# analog_homoThermistor_1xChannel_R1.net
KiCad netlist of a schematic drawn in EAGLE
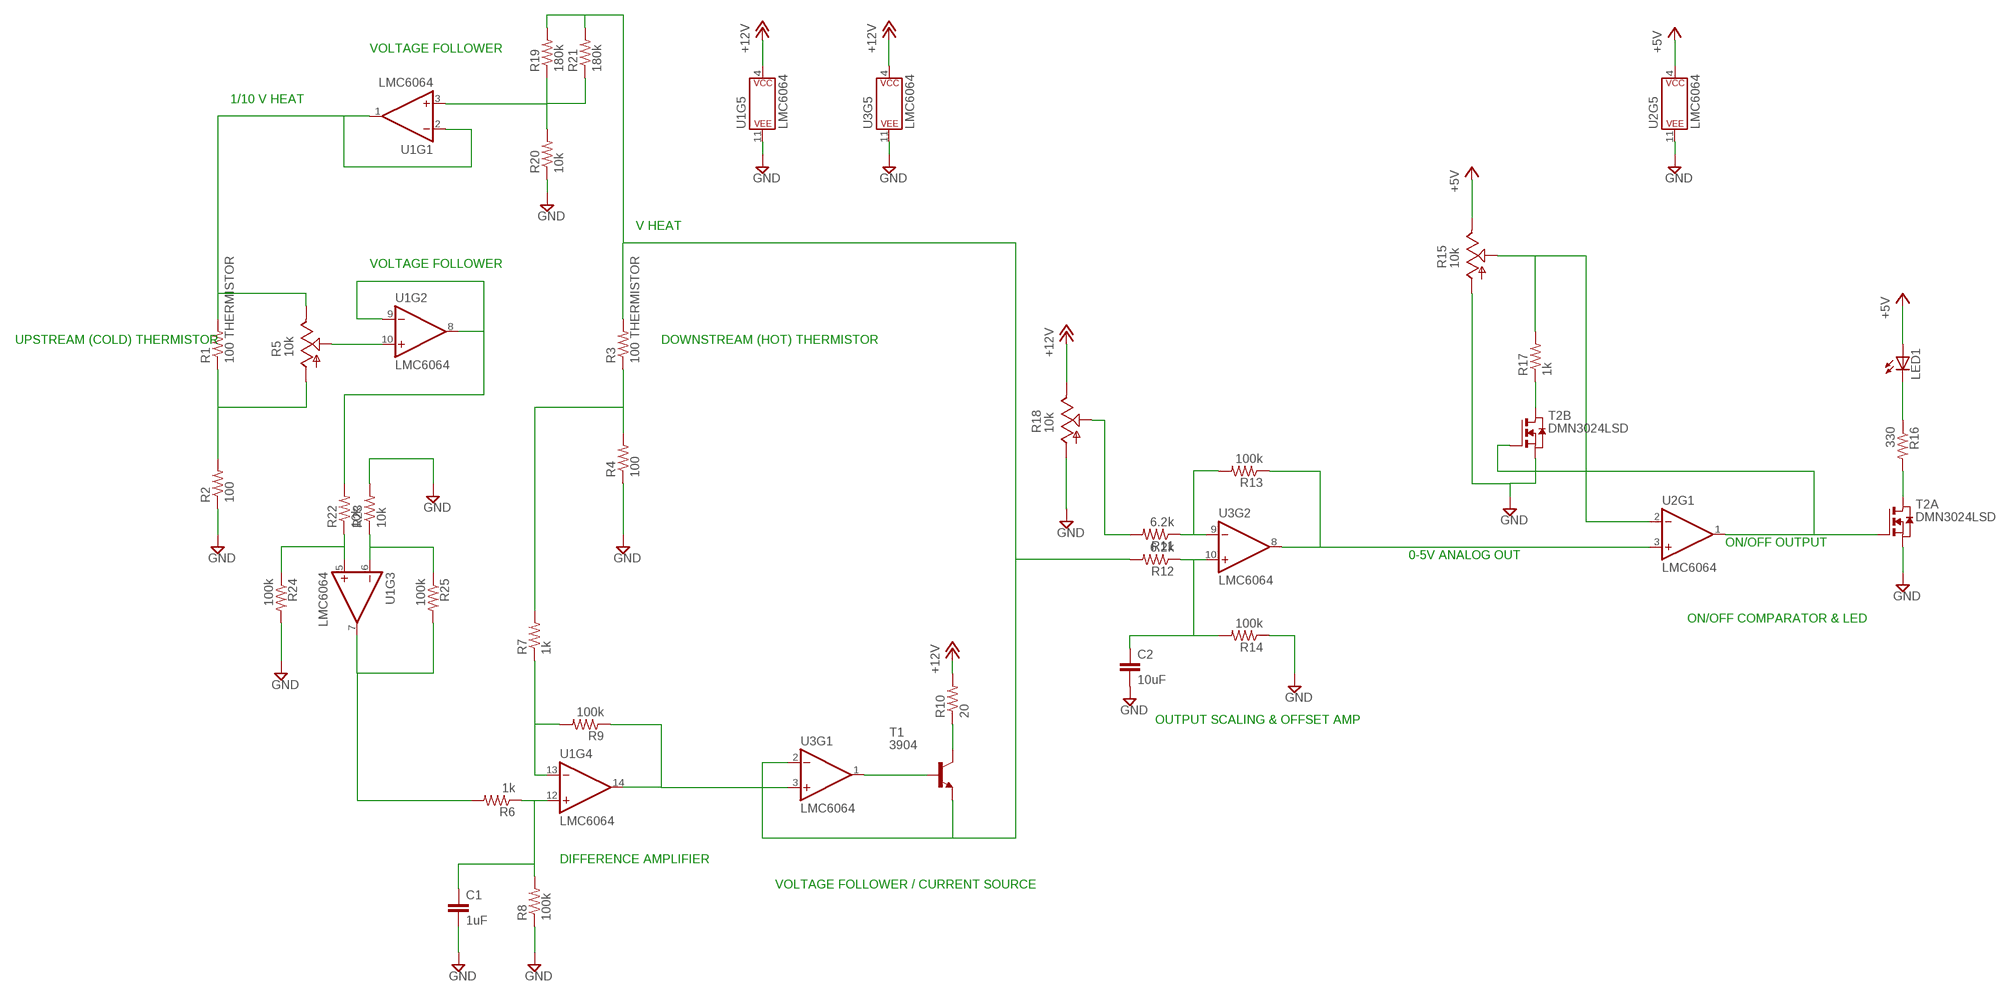
[diagram p0: schematic, sheet 1]

(export (version "E")
  (design (tool "Eeschema 10.0.6"))
  (components
    (comp (ref "C1")
      (value "1uF")
      (footprint "eagle-import:C0603")
      (fields
        (field (name "MF") "Murata Electronics North America")
        (field (name "MPN") "GRM188R61C105KA93D")
      )
      (libsource (lib "eagle-import") (part "C-EUC0603"))
    )
    (comp (ref "C2")
      (value "10uF")
      (footprint "eagle-import:C0603")
      (fields
        (field (name "MF") "Murata Electronics North America")
        (field (name "MPN") "GRM188C81C106MA73D")
      )
      (libsource (lib "eagle-import") (part "C-EUC0603"))
    )
    (comp (ref "LED1")
      (value "LEDCHIPLED_1206")
      (footprint "eagle-import:CHIPLED_1206")
      (fields (field (name "MF") "Lite-On Inc.") (field (name "MPN") "LTST-C150GKT"))
      (libsource (lib "eagle-import") (part "LEDCHIPLED_1206"))
    )
    (comp (ref "R1")
      (value "100 THERMISTOR")
      (footprint "eagle-import:R0603")
      (fields
        (field (name "DISTR") "Digikey")
        (field (name "DISTRPN") "490-2434-1-ND")
        (field (name "MF") "Murata Electronics North America")
        (field (name "MPN") "NCP18XF101J03RB")
      )
      (libsource (lib "eagle-import") (part "R-US_R0603"))
    )
    (comp (ref "R2")
      (value "100")
      (footprint "eagle-import:R0603")
      (fields (field (name "MF") "Panasonic Electronic Components") (field (name "MPN") "ERJ-PA3F1000V"))
      (libsource (lib "eagle-import") (part "R-US_R0603"))
    )
    (comp (ref "R3")
      (value "100 THERMISTOR")
      (footprint "eagle-import:R0603")
      (fields
        (field (name "DISTR") "Digikey")
        (field (name "DISTRPN") "490-2434-1-ND")
        (field (name "MF") "Murata Electronics North America")
        (field (name "MPN") "NCP18XF101J03RB")
      )
      (libsource (lib "eagle-import") (part "R-US_R0603"))
    )
    (comp (ref "R4")
      (value "100")
      (footprint "eagle-import:R0603")
      (fields (field (name "MF") "Panasonic Electronic Components") (field (name "MPN") "ERJ-PA3F1000V"))
      (libsource (lib "eagle-import") (part "R-US_R0603"))
    )
    (comp (ref "R5")
      (value "10k")
      (footprint "eagle-import:SM-42_43W")
      (fields (field (name "MF") "Copal Electronics Inc.") (field (name "MPN") "SM-42TW103"))
      (libsource (lib "eagle-import") (part "TRIM_US-SM-42/43W"))
    )
    (comp (ref "R6")
      (value "1k")
      (footprint "eagle-import:R0603")
      (fields (field (name "MF") "Panasonic Electronic Components") (field (name "MPN") "ERJ-PA3F1001V"))
      (libsource (lib "eagle-import") (part "R-US_R0603"))
    )
    (comp (ref "R7")
      (value "1k")
      (footprint "eagle-import:R0603")
      (fields (field (name "MF") "Panasonic Electronic Components") (field (name "MPN") "ERJ-PA3F1001V"))
      (libsource (lib "eagle-import") (part "R-US_R0603"))
    )
    (comp (ref "R8")
      (value "100k")
      (footprint "eagle-import:R0603")
      (fields (field (name "MF") "Panasonic Electronic Components") (field (name "MPN") "ERJ-PA3F1003V"))
      (libsource (lib "eagle-import") (part "R-US_R0603"))
    )
    (comp (ref "R9")
      (value "100k")
      (footprint "eagle-import:R0603")
      (fields (field (name "MF") "Panasonic Electronic Components") (field (name "MPN") "ERJ-PA3F1003V"))
      (libsource (lib "eagle-import") (part "R-US_R0603"))
    )
    (comp (ref "R10")
      (value "20")
      (footprint "eagle-import:R0603")
      (fields (field (name "MF") "Panasonic Electronic Components") (field (name "MPN") "ERJ-PA3F20R0V"))
      (libsource (lib "eagle-import") (part "R-US_R0603"))
    )
    (comp (ref "R11")
      (value "6.2k")
      (footprint "eagle-import:R0603")
      (fields (field (name "MF") "Panasonic Electronic Components") (field (name "MPN") "ERJ-PA3F6201V"))
      (libsource (lib "eagle-import") (part "R-US_R0603"))
    )
    (comp (ref "R12")
      (value "6.2k")
      (footprint "eagle-import:R0603")
      (fields (field (name "MF") "Panasonic Electronic Components") (field (name "MPN") "ERJ-PA3F6201V"))
      (libsource (lib "eagle-import") (part "R-US_R0603"))
    )
    (comp (ref "R13")
      (value "100k")
      (footprint "eagle-import:R0603")
      (fields (field (name "MF") "Panasonic Electronic Components") (field (name "MPN") "ERJ-PA3F1003V"))
      (libsource (lib "eagle-import") (part "R-US_R0603"))
    )
    (comp (ref "R14")
      (value "100k")
      (footprint "eagle-import:R0603")
      (fields (field (name "MF") "Panasonic Electronic Components") (field (name "MPN") "ERJ-PA3F1003V"))
      (libsource (lib "eagle-import") (part "R-US_R0603"))
    )
    (comp (ref "R15")
      (value "10k")
      (footprint "eagle-import:SM-42_43W")
      (fields (field (name "MF") "Copal Electronics Inc.") (field (name "MPN") "SM-42TW103"))
      (libsource (lib "eagle-import") (part "TRIM_US-SM-42/43W"))
    )
    (comp (ref "R16")
      (value "330")
      (footprint "eagle-import:R0603")
      (fields (field (name "MF") "Panasonic Electronic Components") (field (name "MPN") "ERJ-PA3F3300V"))
      (libsource (lib "eagle-import") (part "R-US_R0603"))
    )
    (comp (ref "R17")
      (value "1k")
      (footprint "eagle-import:R0603")
      (fields (field (name "MF") "Panasonic Electronic Components") (field (name "MPN") "ERJ-PA3F1001V"))
      (libsource (lib "eagle-import") (part "R-US_R0603"))
    )
    (comp (ref "R18")
      (value "10k")
      (footprint "eagle-import:SM-42_43W")
      (fields (field (name "MF") "Copal Electronics Inc.") (field (name "MPN") "SM-42TW103"))
      (libsource (lib "eagle-import") (part "TRIM_US-SM-42/43W"))
    )
    (comp (ref "R19")
      (value "180k")
      (footprint "eagle-import:R0603")
      (fields (field (name "MF") "Panasonic Electronic Components") (field (name "MPN") "ERJ-PA3F1803V"))
      (libsource (lib "eagle-import") (part "R-US_R0603"))
    )
    (comp (ref "R20")
      (value "10k")
      (footprint "eagle-import:R0603")
      (fields (field (name "MF") "Panasonic Electronic Components") (field (name "MPN") "ERJ-PA3F1002V"))
      (libsource (lib "eagle-import") (part "R-US_R0603"))
    )
    (comp (ref "R21")
      (value "180k")
      (footprint "eagle-import:R0603")
      (fields (field (name "MF") "Panasonic Electronic Components") (field (name "MPN") "ERJ-PA3F1803V"))
      (libsource (lib "eagle-import") (part "R-US_R0603"))
    )
    (comp (ref "R22")
      (value "10k")
      (footprint "eagle-import:R0603")
      (fields (field (name "MF") "Panasonic Electronic Components") (field (name "MPN") "ERJ-PA3F1002V"))
      (libsource (lib "eagle-import") (part "R-US_R0603"))
    )
    (comp (ref "R23")
      (value "10k")
      (footprint "eagle-import:R0603")
      (fields (field (name "MF") "Panasonic Electronic Components") (field (name "MPN") "ERJ-PA3F1002V"))
      (libsource (lib "eagle-import") (part "R-US_R0603"))
    )
    (comp (ref "R24")
      (value "100k")
      (footprint "eagle-import:R0603")
      (fields (field (name "MF") "Panasonic Electronic Components") (field (name "MPN") "ERJ-PA3F1003V"))
      (libsource (lib "eagle-import") (part "R-US_R0603"))
    )
    (comp (ref "R25")
      (value "100k")
      (footprint "eagle-import:R0603")
      (fields (field (name "MF") "Panasonic Electronic Components") (field (name "MPN") "ERJ-PA3F1003V"))
      (libsource (lib "eagle-import") (part "R-US_R0603"))
    )
    (comp (ref "T1")
      (value "3904")
      (footprint "eagle-import:SOT23-BEC")
      (fields (field (name "MF") "Fairchild/ON Semiconductor") (field (name "MPN") "MMBT3904"))
      (libsource (lib "eagle-import") (part "-NPN-SOT23-BECMMBT3904LT1"))
    )
    (comp (ref "T2")
      (value "DMN3024LSD")
      (footprint "eagle-import:SO8")
      (fields
        (field (name "MF") "Diodes Incorporated")
        (field (name "MPN") "DMN3024LSD-13")
        (field (name "DISTR") "Digikey")
        (field (name "DISTRPN") "DMN3024LSD-13DICT-ND")
      )
      (libsource (lib "eagle-import") (part "DMN3024LSD"))
    )
    (comp (ref "U1")
      (value "LMC6064")
      (footprint "eagle-import:SO14")
      (fields
        (field (name "DISTR") "Digikey")
        (field (name "DISTRPN") "296-35438-1-ND")
        (field (name "MF") "Texas Instruments")
        (field (name "MPN") "LMC6064AIMX/NOPB")
      )
      (libsource (lib "eagle-import") (part "LMC6064"))
    )
    (comp (ref "U2")
      (value "LMC6064")
      (footprint "eagle-import:SO14")
      (fields
        (field (name "MF") "Texas Instruments")
        (field (name "MPN") "LMC6064AIMX/NOPB")
        (field (name "DISTR") "Digikey")
        (field (name "DISTRPN") "296-35438-1-ND")
      )
      (libsource (lib "eagle-import") (part "LMC6064"))
    )
    (comp (ref "U3")
      (value "LMC6064")
      (footprint "eagle-import:SO14")
      (fields
        (field (name "DISTR") "Digikey")
        (field (name "DISTRPN") "296-35438-1-ND")
        (field (name "MF") "Texas Instruments")
        (field (name "MPN") "LMC6064AIMX/NOPB")
      )
      (libsource (lib "eagle-import") (part "LMC6064"))
    )
  )
  (nets
    (net (code "1") (name "+5V") (class "Default")
      (node (ref "LED1") (pin "A") (pinfunction "A_A") (pintype "passive"))
      (node (ref "R15") (pin "3") (pinfunction "E_3") (pintype "passive"))
      (node (ref "U2") (pin "4") (pinfunction "P$V+_4") (pintype "bidirectional"))
    )
    (net (code "2") (name "+12V") (class "Default")
      (node (ref "R10") (pin "2") (pinfunction "2_2") (pintype "passive"))
      (node (ref "R18") (pin "3") (pinfunction "E_3") (pintype "passive"))
      (node (ref "U1") (pin "4") (pinfunction "P$V+_4") (pintype "bidirectional"))
      (node (ref "U3") (pin "4") (pinfunction "P$V+_4") (pintype "bidirectional"))
    )
    (net (code "3") (name "GND") (class "Default")
      (node (ref "C1") (pin "2") (pinfunction "2_2") (pintype "passive"))
      (node (ref "C2") (pin "2") (pinfunction "2_2") (pintype "passive"))
      (node (ref "R14") (pin "1") (pinfunction "1_1") (pintype "passive"))
      (node (ref "R15") (pin "1") (pinfunction "A_1") (pintype "passive"))
      (node (ref "R18") (pin "1") (pinfunction "A_1") (pintype "passive"))
      (node (ref "R2") (pin "1") (pinfunction "1_1") (pintype "passive"))
      (node (ref "R20") (pin "1") (pinfunction "1_1") (pintype "passive"))
      (node (ref "R23") (pin "2") (pinfunction "2_2") (pintype "passive"))
      (node (ref "R24") (pin "2") (pinfunction "2_2") (pintype "passive"))
      (node (ref "R4") (pin "1") (pinfunction "1_1") (pintype "passive"))
      (node (ref "R8") (pin "1") (pinfunction "1_1") (pintype "passive"))
      (node (ref "T2") (pin "1") (pinfunction "S_1") (pintype "passive"))
      (node (ref "T2") (pin "3") (pinfunction "S_3") (pintype "passive"))
      (node (ref "U1") (pin "11") (pinfunction "P$V-_11") (pintype "bidirectional"))
      (node (ref "U2") (pin "11") (pinfunction "P$V-_11") (pintype "bidirectional"))
      (node (ref "U3") (pin "11") (pinfunction "P$V-_11") (pintype "bidirectional"))
    )
    (net (code "4") (name "Net-(LED1-PadC)") (class "Default")
      (node (ref "LED1") (pin "C") (pinfunction "C_C") (pintype "passive"))
      (node (ref "R16") (pin "1") (pinfunction "1_1") (pintype "passive"))
    )
    (net (code "5") (name "Net-(R3-Pad1)") (class "Default")
      (node (ref "R3") (pin "1") (pinfunction "1_1") (pintype "passive"))
      (node (ref "R4") (pin "2") (pinfunction "2_2") (pintype "passive"))
      (node (ref "R7") (pin "2") (pinfunction "2_2") (pintype "passive"))
    )
    (net (code "6") (name "Net-(R5-A)") (class "Default")
      (node (ref "R1") (pin "1") (pinfunction "1_1") (pintype "passive"))
      (node (ref "R2") (pin "2") (pinfunction "2_2") (pintype "passive"))
      (node (ref "R5") (pin "1") (pinfunction "A_1") (pintype "passive"))
    )
    (net (code "7") (name "Net-(R5-E)") (class "Default")
      (node (ref "R1") (pin "2") (pinfunction "2_2") (pintype "passive"))
      (node (ref "R5") (pin "3") (pinfunction "E_3") (pintype "passive"))
      (node (ref "U1") (pin "1") (pinfunction "OUT_1") (pintype "output"))
      (node (ref "U1") (pin "2") (pinfunction "-IN_2") (pintype "input"))
    )
    (net (code "8") (name "Net-(R5-S)") (class "Default")
      (node (ref "R5") (pin "2") (pinfunction "S_2") (pintype "passive"))
      (node (ref "U1") (pin "10") (pinfunction "+IN_10") (pintype "input"))
    )
    (net (code "9") (name "Net-(R10-Pad1)") (class "Default")
      (node (ref "R10") (pin "1") (pinfunction "1_1") (pintype "passive"))
      (node (ref "T1") (pin "C") (pinfunction "C_C") (pintype "passive"))
    )
    (net (code "10") (name "Net-(R15-S)") (class "Default")
      (node (ref "R15") (pin "2") (pinfunction "S_2") (pintype "passive"))
      (node (ref "R17") (pin "2") (pinfunction "2_2") (pintype "passive"))
      (node (ref "U2") (pin "2") (pinfunction "-IN_2") (pintype "input"))
    )
    (net (code "11") (name "Net-(R16-Pad2)") (class "Default")
      (node (ref "R16") (pin "2") (pinfunction "2_2") (pintype "passive"))
      (node (ref "T2") (pin "7") (pinfunction "D_7") (pintype "passive"))
      (node (ref "T2") (pin "8") (pinfunction "D_8") (pintype "passive"))
    )
    (net (code "12") (name "Net-(R17-Pad1)") (class "Default")
      (node (ref "R17") (pin "1") (pinfunction "1_1") (pintype "passive"))
      (node (ref "T2") (pin "5") (pinfunction "D_5") (pintype "passive"))
      (node (ref "T2") (pin "6") (pinfunction "D_6") (pintype "passive"))
    )
    (net (code "13") (name "Net-(R18-S)") (class "Default")
      (node (ref "R11") (pin "2") (pinfunction "2_2") (pintype "passive"))
      (node (ref "R18") (pin "2") (pinfunction "S_2") (pintype "passive"))
    )
    (net (code "14") (name "Net-(T2A-G)") (class "Default")
      (node (ref "T2") (pin "2") (pinfunction "G_2") (pintype "passive"))
      (node (ref "T2") (pin "4") (pinfunction "G_4") (pintype "passive"))
      (node (ref "U2") (pin "1") (pinfunction "OUT_1") (pintype "output"))
    )
    (net (code "15") (name "Net-(U1A-+IN)") (class "Default")
      (node (ref "R19") (pin "1") (pinfunction "1_1") (pintype "passive"))
      (node (ref "R20") (pin "2") (pinfunction "2_2") (pintype "passive"))
      (node (ref "R21") (pin "1") (pinfunction "1_1") (pintype "passive"))
      (node (ref "U1") (pin "3") (pinfunction "+IN_3") (pintype "input"))
    )
    (net (code "16") (name "Net-(U1B--IN)") (class "Default")
      (node (ref "R22") (pin "2") (pinfunction "2_2") (pintype "passive"))
      (node (ref "U1") (pin "8") (pinfunction "OUT_8") (pintype "output"))
      (node (ref "U1") (pin "9") (pinfunction "-IN_9") (pintype "input"))
    )
    (net (code "17") (name "Net-(U1C-+IN)") (class "Default")
      (node (ref "R22") (pin "1") (pinfunction "1_1") (pintype "passive"))
      (node (ref "R24") (pin "1") (pinfunction "1_1") (pintype "passive"))
      (node (ref "U1") (pin "5") (pinfunction "+IN_5") (pintype "input"))
    )
    (net (code "18") (name "Net-(U1C--IN)") (class "Default")
      (node (ref "R23") (pin "1") (pinfunction "1_1") (pintype "passive"))
      (node (ref "R25") (pin "1") (pinfunction "1_1") (pintype "passive"))
      (node (ref "U1") (pin "6") (pinfunction "-IN_6") (pintype "input"))
    )
    (net (code "19") (name "Net-(U1C-OUT)") (class "Default")
      (node (ref "R25") (pin "2") (pinfunction "2_2") (pintype "passive"))
      (node (ref "R6") (pin "2") (pinfunction "2_2") (pintype "passive"))
      (node (ref "U1") (pin "7") (pinfunction "OUT_7") (pintype "output"))
    )
    (net (code "20") (name "Net-(U1D-+IN)") (class "Default")
      (node (ref "C1") (pin "1") (pinfunction "1_1") (pintype "passive"))
      (node (ref "R6") (pin "1") (pinfunction "1_1") (pintype "passive"))
      (node (ref "R8") (pin "2") (pinfunction "2_2") (pintype "passive"))
      (node (ref "U1") (pin "12") (pinfunction "+IN_12") (pintype "input"))
    )
    (net (code "21") (name "Net-(U1D--IN)") (class "Default")
      (node (ref "R7") (pin "1") (pinfunction "1_1") (pintype "passive"))
      (node (ref "R9") (pin "2") (pinfunction "2_2") (pintype "passive"))
      (node (ref "U1") (pin "13") (pinfunction "-IN_13") (pintype "input"))
    )
    (net (code "22") (name "Net-(U1D-OUT)") (class "Default")
      (node (ref "R9") (pin "1") (pinfunction "1_1") (pintype "passive"))
      (node (ref "U1") (pin "14") (pinfunction "OUT_14") (pintype "output"))
      (node (ref "U3") (pin "3") (pinfunction "+IN_3") (pintype "input"))
    )
    (net (code "23") (name "Net-(U2A-+IN)") (class "Default")
      (node (ref "R13") (pin "1") (pinfunction "1_1") (pintype "passive"))
      (node (ref "U2") (pin "3") (pinfunction "+IN_3") (pintype "input"))
      (node (ref "U3") (pin "8") (pinfunction "OUT_8") (pintype "output"))
    )
    (net (code "24") (name "Net-(U3A--IN)") (class "Default")
      (node (ref "R12") (pin "2") (pinfunction "2_2") (pintype "passive"))
      (node (ref "R19") (pin "2") (pinfunction "2_2") (pintype "passive"))
      (node (ref "R21") (pin "2") (pinfunction "2_2") (pintype "passive"))
      (node (ref "R3") (pin "2") (pinfunction "2_2") (pintype "passive"))
      (node (ref "T1") (pin "E") (pinfunction "E_E") (pintype "passive"))
      (node (ref "U3") (pin "2") (pinfunction "-IN_2") (pintype "input"))
    )
    (net (code "25") (name "Net-(U3A-OUT)") (class "Default")
      (node (ref "T1") (pin "B") (pinfunction "B_B") (pintype "passive"))
      (node (ref "U3") (pin "1") (pinfunction "OUT_1") (pintype "output"))
    )
    (net (code "26") (name "Net-(U3B-+IN)") (class "Default")
      (node (ref "C2") (pin "1") (pinfunction "1_1") (pintype "passive"))
      (node (ref "R12") (pin "1") (pinfunction "1_1") (pintype "passive"))
      (node (ref "R14") (pin "2") (pinfunction "2_2") (pintype "passive"))
      (node (ref "U3") (pin "10") (pinfunction "+IN_10") (pintype "input"))
    )
    (net (code "27") (name "Net-(U3B--IN)") (class "Default")
      (node (ref "R11") (pin "1") (pinfunction "1_1") (pintype "passive"))
      (node (ref "R13") (pin "2") (pinfunction "2_2") (pintype "passive"))
      (node (ref "U3") (pin "9") (pinfunction "-IN_9") (pintype "input"))
    )
  )
)
